# CO2_Metar_SCH_1.net
KiCad netlist of a schematic drawn in Altium Designer
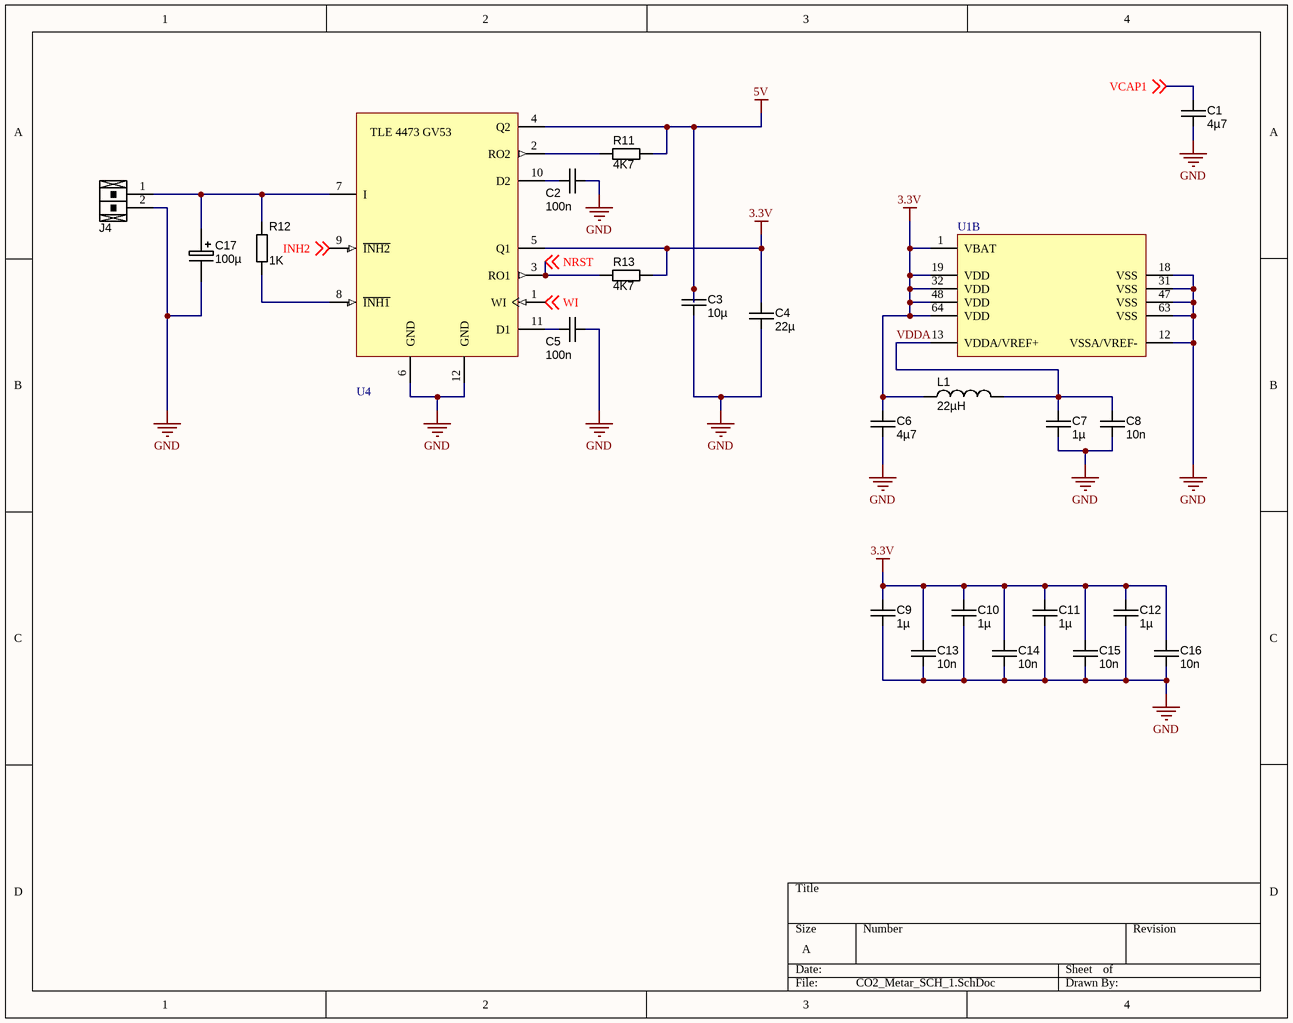
[diagram p0: CO2_Metar_SCH_1.SchDoc]

(export (version "E")
  (design (tool "Eeschema 10.0.6"))
  (components
    (comp (ref "C1")
      (value "4µ7")
      (footprint "CAPC2012X135N")
      (description "Capacitor SMD Cer 4.7uF 10% 16V X5R 0805")
      (fields (field (name "TOLERANCE") "±10%") (field (name "Comment") "approved sub OK"))
      (libsource (lib "PBL - Capacitors") (part "CAPC_4u7_0805"))
    )
    (comp (ref "C2")
      (value "100n")
      (footprint "CAPC1608X90N")
      (description "Capacitor SMD Cer 100nF 10% 50V X7R 0603")
      (fields (field (name "TOLERANCE") "±10%") (field (name "Comment") "approved sub OK"))
      (libsource (lib "PBL - Capacitors") (part "CAPC_100n_0603_X7R_50V_10%"))
    )
    (comp (ref "C3")
      (value "10µ")
      (footprint "CAPC3225X220N")
      (description "Capacitor SMD Cer 10uF 20% 16V X5R 1210")
      (fields (field (name "TOLERANCE") "±20%"))
      (libsource (lib "PBL - Capacitors") (part "CAPC_10u_1210_50V"))
    )
    (comp (ref "C4")
      (value "22µ")
      (footprint "CAPC4532X280N")
      (description "Capacitor SMD Cer 22uF 20% 25V X5R 1812")
      (fields (field (name "TOLERANCE") "±20%") (field (name "Comment") "approved sub OK"))
      (libsource (lib "PBL - Capacitors") (part "CAPC_22u_1812_25V"))
    )
    (comp (ref "C5")
      (value "100n")
      (footprint "CAPC1608X90N")
      (description "Capacitor SMD Cer 100nF 10% 50V X7R 0603")
      (fields (field (name "TOLERANCE") "±10%") (field (name "Comment") "approved sub OK"))
      (libsource (lib "PBL - Capacitors") (part "CAPC_100n_0603_X7R_50V_10%"))
    )
    (comp (ref "C6")
      (value "4µ7")
      (footprint "CAPC2012X135N")
      (description "Capacitor SMD Cer 4.7uF 10% 16V X5R 0805")
      (fields (field (name "TOLERANCE") "±10%") (field (name "Comment") "approved sub OK"))
      (libsource (lib "PBL - Capacitors") (part "CAPC_4u7_0805"))
    )
    (comp (ref "C7")
      (value "1µ")
      (footprint "CAPC2012X135N")
      (description "Capacitor SMD Cer 1uF 10% 16V X7R 0805")
      (fields (field (name "TOLERANCE") "±10%") (field (name "Comment") "approved sub OK"))
      (libsource (lib "PBL - Capacitors") (part "CAPC_1u_0805_X7R_16V_10%"))
    )
    (comp (ref "C8")
      (value "10n")
      (footprint "CAPC1608X90N")
      (description "Capacitor SMD Cer 10nF 10% 50V X7R 0603")
      (fields (field (name "TOLERANCE") "±10%") (field (name "Comment") "approved sub OK"))
      (libsource (lib "PBL - Capacitors") (part "CAPC_10n_0603_X7R_50V_10%"))
    )
    (comp (ref "C9")
      (value "1µ")
      (footprint "CAPC2012X135N")
      (description "Capacitor SMD Cer 1uF 10% 16V X7R 0805")
      (fields (field (name "TOLERANCE") "±10%") (field (name "Comment") "approved sub OK"))
      (libsource (lib "PBL - Capacitors") (part "CAPC_1u_0805_X7R_16V_10%"))
    )
    (comp (ref "C10")
      (value "1µ")
      (footprint "CAPC2012X135N")
      (description "Capacitor SMD Cer 1uF 10% 16V X7R 0805")
      (fields (field (name "TOLERANCE") "±10%") (field (name "Comment") "approved sub OK"))
      (libsource (lib "PBL - Capacitors") (part "CAPC_1u_0805_X7R_16V_10%"))
    )
    (comp (ref "C11")
      (value "1µ")
      (footprint "CAPC2012X135N")
      (description "Capacitor SMD Cer 1uF 10% 16V X7R 0805")
      (fields (field (name "TOLERANCE") "±10%") (field (name "Comment") "approved sub OK"))
      (libsource (lib "PBL - Capacitors") (part "CAPC_1u_0805_X7R_16V_10%"))
    )
    (comp (ref "C12")
      (value "1µ")
      (footprint "CAPC2012X135N")
      (description "Capacitor SMD Cer 1uF 10% 16V X7R 0805")
      (fields (field (name "TOLERANCE") "±10%") (field (name "Comment") "approved sub OK"))
      (libsource (lib "PBL - Capacitors") (part "CAPC_1u_0805_X7R_16V_10%"))
    )
    (comp (ref "C13")
      (value "10n")
      (footprint "CAPC1608X90N")
      (description "Capacitor SMD Cer 10nF 10% 50V X7R 0603")
      (fields (field (name "TOLERANCE") "±10%") (field (name "Comment") "approved sub OK"))
      (libsource (lib "PBL - Capacitors") (part "CAPC_10n_0603_X7R_50V_10%"))
    )
    (comp (ref "C14")
      (value "10n")
      (footprint "CAPC1608X90N")
      (description "Capacitor SMD Cer 10nF 10% 50V X7R 0603")
      (fields (field (name "TOLERANCE") "±10%") (field (name "Comment") "approved sub OK"))
      (libsource (lib "PBL - Capacitors") (part "CAPC_10n_0603_X7R_50V_10%"))
    )
    (comp (ref "C15")
      (value "10n")
      (footprint "CAPC1608X90N")
      (description "Capacitor SMD Cer 10nF 10% 50V X7R 0603")
      (fields (field (name "TOLERANCE") "±10%") (field (name "Comment") "approved sub OK"))
      (libsource (lib "PBL - Capacitors") (part "CAPC_10n_0603_X7R_50V_10%"))
    )
    (comp (ref "C16")
      (value "10n")
      (footprint "CAPC1608X90N")
      (description "Capacitor SMD Cer 10nF 10% 50V X7R 0603")
      (fields (field (name "TOLERANCE") "±10%") (field (name "Comment") "approved sub OK"))
      (libsource (lib "PBL - Capacitors") (part "CAPC_10n_0603_X7R_50V_10%"))
    )
    (comp (ref "C17")
      (value "100µ")
      (footprint "CAPAE200P550X1200_FLAT2")
      (description "Capacitor THD Electrolytic 100uF 20% 16V Radial")
      (fields (field (name "TOLERANCE") "±20%") (field (name "MANUFACTURER") "Panasonic - ECG"))
      (libsource (lib "PBL - Capacitors") (part "CAPE_100u_16V_THD"))
    )
    (comp (ref "J4")
      (value "*")
      (footprint "2P_PCB_TERM_BLOCK_HDR")
      (description "Terminal Block THT 2-position header 3.81mm pitch")
      (fields (field (name "VOLTAGE") "300V"))
      (libsource (lib "PBL - Connectors") (part "2P_TERM_BLOCK_HEADER"))
    )
    (comp (ref "L1")
      (value "22µH")
      (footprint "IND_Coilcraft_DO3316P_SM")
      (description "Inductor Power SMD 22µH")
      (fields (field (name "TOLERANCE") "±10%"))
      (libsource (lib "PBL - Inductors") (part "INDC_22u_DO3316P-223"))
    )
    (comp (ref "R11")
      (value "4K7")
      (footprint "RESC1608X55N")
      (description "Resistor SMD chip 4.7k Ohm 0.1W 5% 0603")
      (fields (field (name "TOLERANCE") "±5%") (field (name "Comment") "Thick Film"))
      (libsource (lib "PBL - Resistors") (part "RES_4K7_0603_5%"))
    )
    (comp (ref "R12")
      (value "1K")
      (footprint "RESC1608X55N")
      (description "Resistor SMD chip 1k Ohm 0.1W 5% 0603")
      (fields (field (name "TOLERANCE") "±5%") (field (name "Comment") "Thick Film"))
      (libsource (lib "PBL - Resistors") (part "RES_1K_0603_5%"))
    )
    (comp (ref "R13")
      (value "4K7")
      (footprint "RESC1608X55N")
      (description "Resistor SMD chip 4.7k Ohm 0.1W 5% 0603")
      (fields (field (name "TOLERANCE") "±5%") (field (name "Comment") "Thick Film"))
      (libsource (lib "PBL - Resistors") (part "RES_4K7_0603_5%"))
    )
    (comp (ref "U1")
      (value "~")
      (footprint "STM-LQFP64_N")
      (fields (field (name "MANUFACTURER") "STMicroelectronics") (field (name "PARTNUMBER") "STM32F401RBT6"))
      (libsource (lib "STMicroelectronics STM32 F4") (part "STM32F401RBT6"))
    )
    (comp (ref "U4")
      (value "*")
      (footprint "PG-DSO-12NTS")
      (description "Dual Low Drop Voltage Regulator")
      (libsource (lib "co2_meter_integrated_library") (part "TLE4473-GV53"))
    )
  )
  (nets
    (net (code "1") (name "/VDDA") (class "Default")
      (node (ref "C7") (pin "1") (pintype "passive"))
      (node (ref "C8") (pin "1") (pintype "passive"))
      (node (ref "L1") (pin "2") (pinfunction "2_2") (pintype "passive"))
      (node (ref "U1") (pin "13") (pinfunction "VDDA/VREF+_13") (pintype "power_in"))
    )
    (net (code "2") (name "3.3V") (class "Default")
      (node (ref "C10") (pin "1") (pintype "passive"))
      (node (ref "C11") (pin "1") (pintype "passive"))
      (node (ref "C12") (pin "1") (pintype "passive"))
      (node (ref "C13") (pin "1") (pintype "passive"))
      (node (ref "C14") (pin "1") (pintype "passive"))
      (node (ref "C15") (pin "1") (pintype "passive"))
      (node (ref "C16") (pin "1") (pintype "passive"))
      (node (ref "C4") (pin "1") (pintype "passive"))
      (node (ref "C6") (pin "1") (pintype "passive"))
      (node (ref "C9") (pin "1") (pintype "passive"))
      (node (ref "L1") (pin "1") (pinfunction "1_1") (pintype "passive"))
      (node (ref "R13") (pin "2") (pinfunction "2_2") (pintype "passive"))
      (node (ref "U1") (pin "1") (pinfunction "VBAT_1") (pintype "power_in"))
      (node (ref "U1") (pin "19") (pinfunction "VDD_19") (pintype "power_in"))
      (node (ref "U1") (pin "32") (pinfunction "VDD_32") (pintype "power_in"))
      (node (ref "U1") (pin "48") (pinfunction "VDD_48") (pintype "power_in"))
      (node (ref "U1") (pin "64") (pinfunction "VDD_64") (pintype "power_in"))
      (node (ref "U4") (pin "5") (pinfunction "Q1_5") (pintype "power_in"))
    )
    (net (code "3") (name "5V") (class "Default")
      (node (ref "C3") (pin "1") (pintype "passive"))
      (node (ref "R11") (pin "2") (pinfunction "2_2") (pintype "passive"))
      (node (ref "U4") (pin "4") (pinfunction "Q2_4") (pintype "power_in"))
    )
    (net (code "4") (name "GND") (class "Default")
      (node (ref "C1") (pin "2") (pintype "passive"))
      (node (ref "C10") (pin "2") (pintype "passive"))
      (node (ref "C11") (pin "2") (pintype "passive"))
      (node (ref "C12") (pin "2") (pintype "passive"))
      (node (ref "C13") (pin "2") (pintype "passive"))
      (node (ref "C14") (pin "2") (pintype "passive"))
      (node (ref "C15") (pin "2") (pintype "passive"))
      (node (ref "C16") (pin "2") (pintype "passive"))
      (node (ref "C17") (pin "2") (pintype "passive"))
      (node (ref "C2") (pin "2") (pintype "passive"))
      (node (ref "C3") (pin "2") (pintype "passive"))
      (node (ref "C4") (pin "2") (pintype "passive"))
      (node (ref "C5") (pin "2") (pintype "passive"))
      (node (ref "C6") (pin "2") (pintype "passive"))
      (node (ref "C7") (pin "2") (pintype "passive"))
      (node (ref "C8") (pin "2") (pintype "passive"))
      (node (ref "C9") (pin "2") (pintype "passive"))
      (node (ref "J4") (pin "2") (pinfunction "2_2") (pintype "power_in"))
      (node (ref "U1") (pin "12") (pinfunction "VSSA/VREF-_12") (pintype "power_in"))
      (node (ref "U1") (pin "18") (pinfunction "VSS_18") (pintype "power_in"))
      (node (ref "U1") (pin "31") (pinfunction "VSS_31") (pintype "power_in"))
      (node (ref "U1") (pin "47") (pinfunction "VSS_47") (pintype "power_in"))
      (node (ref "U1") (pin "63") (pinfunction "VSS_63") (pintype "power_in"))
      (node (ref "U4") (pin "12") (pinfunction "GND_12") (pintype "power_in"))
      (node (ref "U4") (pin "6") (pinfunction "GND_6") (pintype "power_in"))
    )
    (net (code "5") (name "INH2") (class "Default")
      (node (ref "U4") (pin "9") (pinfunction "~{INH2}_9") (pintype "input"))
    )
    (net (code "6") (name "NRST") (class "Default")
      (node (ref "R13") (pin "1") (pinfunction "1_1") (pintype "passive"))
      (node (ref "U4") (pin "3") (pinfunction "RO1_3") (pintype "output"))
    )
    (net (code "7") (name "Net-(U4-D1)") (class "Default")
      (node (ref "C5") (pin "1") (pintype "passive"))
      (node (ref "U4") (pin "11") (pinfunction "D1_11") (pintype "passive"))
    )
    (net (code "8") (name "Net-(U4-D2)") (class "Default")
      (node (ref "C2") (pin "1") (pintype "passive"))
      (node (ref "U4") (pin "10") (pinfunction "D2_10") (pintype "passive"))
    )
    (net (code "9") (name "Net-(U4-I)") (class "Default")
      (node (ref "C17") (pin "1") (pintype "passive"))
      (node (ref "J4") (pin "1") (pinfunction "1_1") (pintype "power_in"))
      (node (ref "R12") (pin "1") (pinfunction "1_1") (pintype "passive"))
      (node (ref "U4") (pin "7") (pinfunction "I_7") (pintype "power_in"))
    )
    (net (code "10") (name "Net-(U4-RO2)") (class "Default")
      (node (ref "R11") (pin "1") (pinfunction "1_1") (pintype "passive"))
      (node (ref "U4") (pin "2") (pinfunction "RO2_2") (pintype "output"))
    )
    (net (code "11") (name "Net-(U4-~{INH1})") (class "Default")
      (node (ref "R12") (pin "2") (pinfunction "2_2") (pintype "passive"))
      (node (ref "U4") (pin "8") (pinfunction "~{INH1}_8") (pintype "input"))
    )
    (net (code "12") (name "VCAP1") (class "Default") (node (ref "C1") (pin "1") (pintype "passive")))
    (net (code "13") (name "WI") (class "Default")
      (node (ref "U4") (pin "1") (pinfunction "WI_1") (pintype "input"))
    )
  )
)
